# GPSSDver2.net
KiCad netlist of a schematic drawn in EAGLE
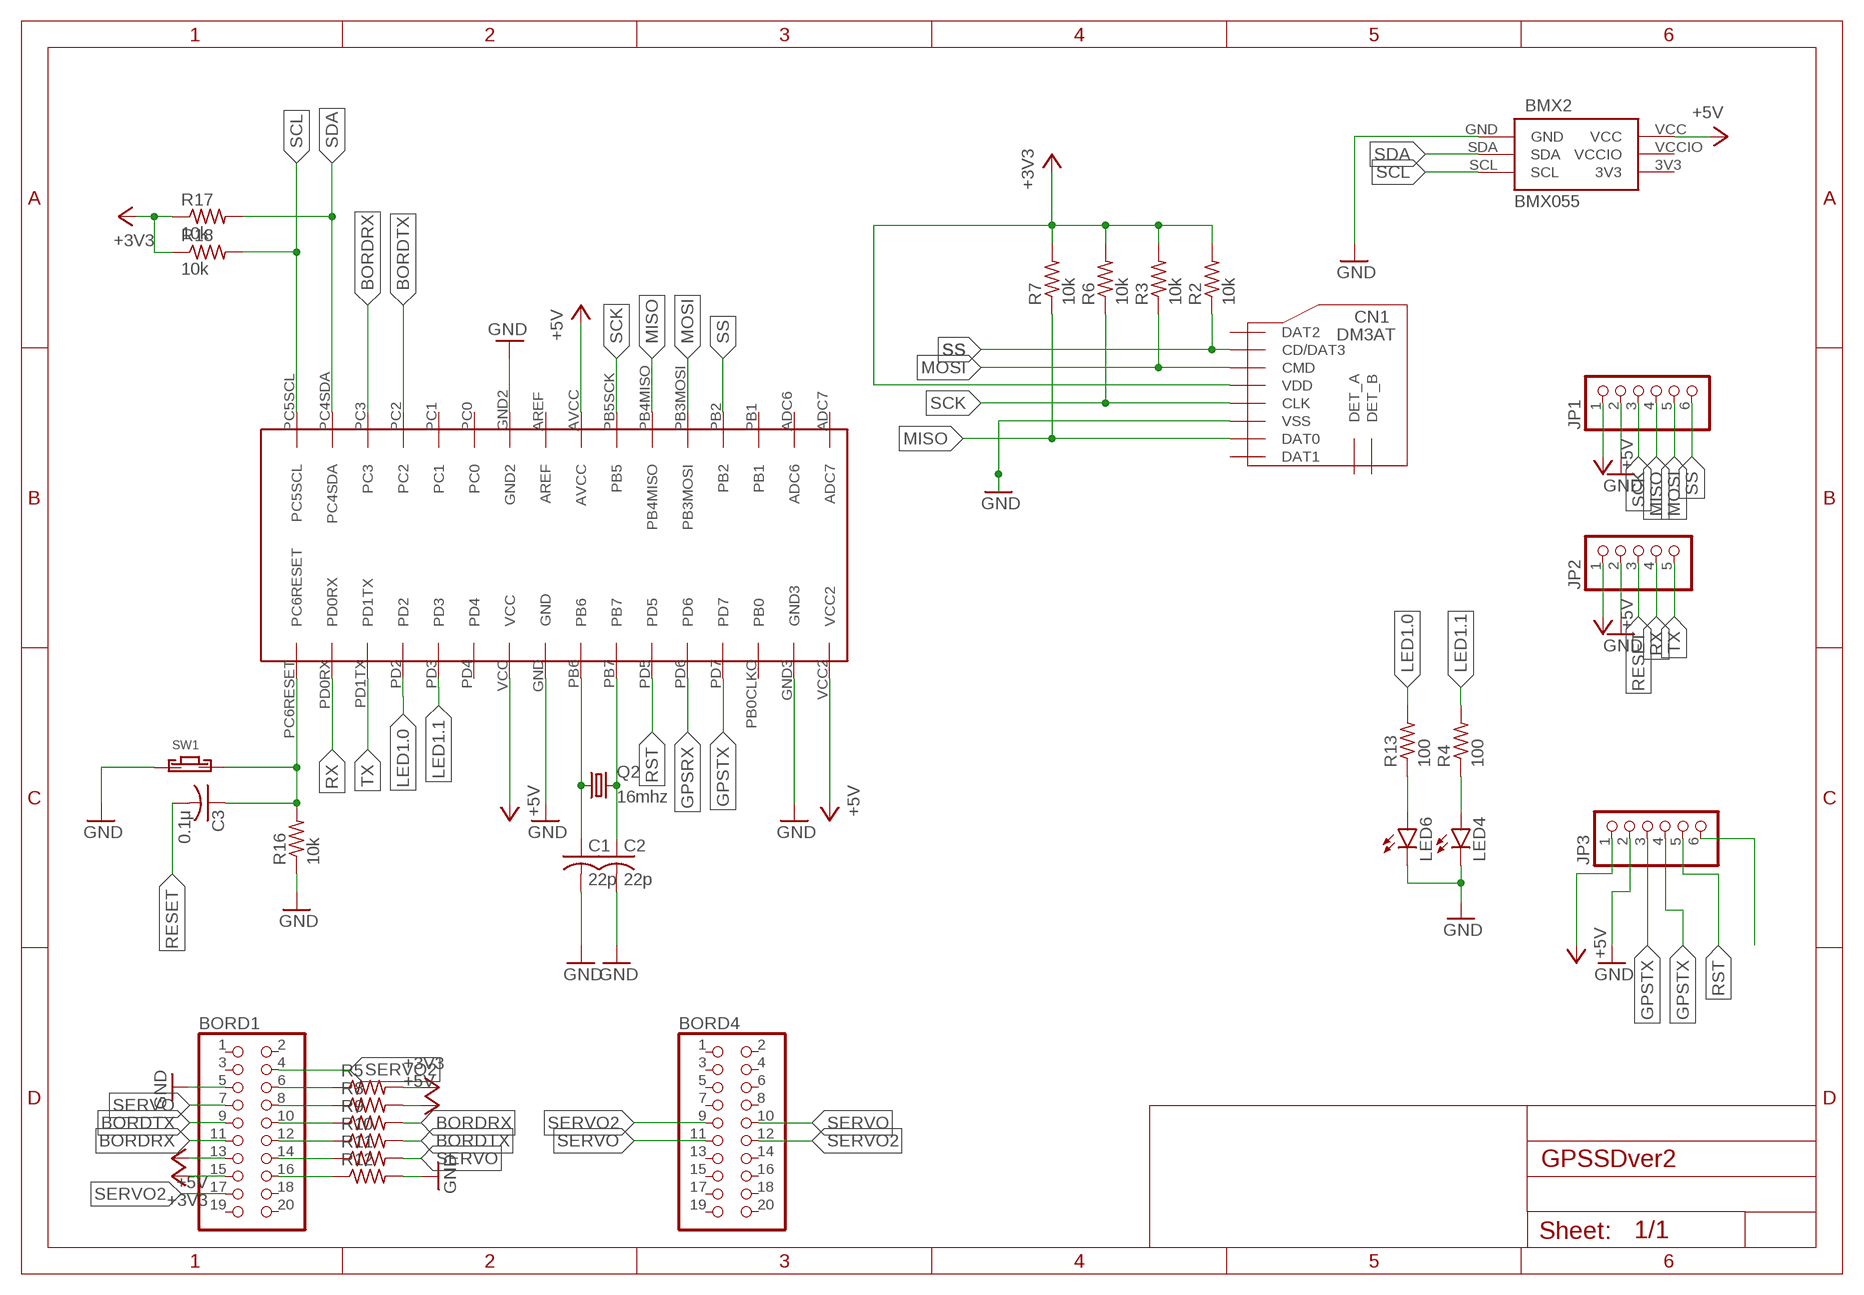
[diagram p0: schematic, sheet 1]

(export (version "E")
  (design (tool "Eeschema 10.0.6"))
  (components
    (comp (ref "BMX2")
      (value "BMX055")
      (footprint "eagle-import:BMX055")
      (libsource (lib "eagle-import") (part "BMX055"))
    )
    (comp (ref "BORD1")
      (value "PINHD-2X10/90")
      (footprint "eagle-import:2X10_90")
      (libsource (lib "eagle-import") (part "PINHD-2X10/90"))
    )
    (comp (ref "BORD4")
      (value "PINHD-2X10/90")
      (footprint "eagle-import:2X10_90")
      (libsource (lib "eagle-import") (part "PINHD-2X10/90"))
    )
    (comp (ref "C1")
      (value "22p")
      (footprint "eagle-import:C1608")
      (libsource (lib "eagle-import") (part "C-USC1608"))
    )
    (comp (ref "C2")
      (value "22p")
      (footprint "eagle-import:C1608")
      (libsource (lib "eagle-import") (part "C-USC1608"))
    )
    (comp (ref "C3")
      (value "0.1μ")
      (footprint "eagle-import:C1608")
      (libsource (lib "eagle-import") (part "C-USC1608"))
    )
    (comp (ref "CN1")
      (value "DM3AT")
      (footprint "eagle-import:DM3AT")
      (libsource (lib "eagle-import") (part "DM3AT"))
    )
    (comp (ref "JP1")
      (value "PINHD-1X6")
      (footprint "eagle-import:1X06")
      (libsource (lib "eagle-import") (part "PINHD-1X6"))
    )
    (comp (ref "JP2")
      (value "PINHD-1X5")
      (footprint "eagle-import:1X05")
      (libsource (lib "eagle-import") (part "PINHD-1X5"))
    )
    (comp (ref "JP3")
      (value "PINHD-1X6")
      (footprint "eagle-import:1X06")
      (libsource (lib "eagle-import") (part "PINHD-1X6"))
    )
    (comp (ref "LED4")
      (value "LED5MM")
      (footprint "eagle-import:LED5MM")
      (libsource (lib "eagle-import") (part "LED5MM"))
    )
    (comp (ref "LED6")
      (value "LED5MM")
      (footprint "eagle-import:LED5MM")
      (libsource (lib "eagle-import") (part "LED5MM"))
    )
    (comp (ref "Q2")
      (value "16mhz")
      (footprint "eagle-import:HC49UP")
      (libsource (lib "eagle-import") (part "CRYSTALHC49UP"))
    )
    (comp (ref "R2")
      (value "10k")
      (footprint "eagle-import:R0603")
      (libsource (lib "eagle-import") (part "R-US_R0603"))
    )
    (comp (ref "R3")
      (value "10k")
      (footprint "eagle-import:R0603")
      (libsource (lib "eagle-import") (part "R-US_R0603"))
    )
    (comp (ref "R4")
      (value "100")
      (footprint "eagle-import:R0603")
      (libsource (lib "eagle-import") (part "R-US_R0603"))
    )
    (comp (ref "R5")
      (value "R-US_R0603")
      (footprint "eagle-import:R0603")
      (libsource (lib "eagle-import") (part "R-US_R0603"))
    )
    (comp (ref "R6")
      (value "10k")
      (footprint "eagle-import:R0603")
      (libsource (lib "eagle-import") (part "R-US_R0603"))
    )
    (comp (ref "R7")
      (value "10k")
      (footprint "eagle-import:R0603")
      (libsource (lib "eagle-import") (part "R-US_R0603"))
    )
    (comp (ref "R8")
      (value "R-US_R0603")
      (footprint "eagle-import:R0603")
      (libsource (lib "eagle-import") (part "R-US_R0603"))
    )
    (comp (ref "R9")
      (value "R-US_R0603")
      (footprint "eagle-import:R0603")
      (libsource (lib "eagle-import") (part "R-US_R0603"))
    )
    (comp (ref "R10")
      (value "R-US_R0603")
      (footprint "eagle-import:R0603")
      (libsource (lib "eagle-import") (part "R-US_R0603"))
    )
    (comp (ref "R11")
      (value "R-US_R0603")
      (footprint "eagle-import:R0603")
      (libsource (lib "eagle-import") (part "R-US_R0603"))
    )
    (comp (ref "R12")
      (value "R-US_R0603")
      (footprint "eagle-import:R0603")
      (libsource (lib "eagle-import") (part "R-US_R0603"))
    )
    (comp (ref "R13")
      (value "100")
      (footprint "eagle-import:R0603")
      (libsource (lib "eagle-import") (part "R-US_R0603"))
    )
    (comp (ref "R16")
      (value "10k")
      (footprint "eagle-import:R0603")
      (libsource (lib "eagle-import") (part "R-US_R0603"))
    )
    (comp (ref "R17")
      (value "10k")
      (footprint "eagle-import:R0603")
      (libsource (lib "eagle-import") (part "R-US_R0603"))
    )
    (comp (ref "R18")
      (value "10k")
      (footprint "eagle-import:R0603")
      (libsource (lib "eagle-import") (part "R-US_R0603"))
    )
    (comp (ref "SW1")
      (value "TVAF06-A020B-R")
      (footprint "eagle-import:TVAF06-A020B-R")
      (libsource (lib "eagle-import") (part "TVAF06-A020B-R"))
    )
    (comp (ref "U$3")
      (value "ATMEGA328P-AU")
      (footprint "eagle-import:ATMEGA328P-AU")
      (libsource (lib "eagle-import") (part "ATMEGA328P-AU"))
    )
  )
  (nets
    (net (code "1") (name "+3V3") (class "Default")
      (node (ref "BORD1") (pin "15") (pinfunction "15_15") (pintype "passive"))
      (node (ref "CN1") (pin "VDD") (pinfunction "VDD_VDD") (pintype "bidirectional"))
      (node (ref "R17") (pin "1") (pinfunction "1_1") (pintype "passive"))
      (node (ref "R18") (pin "1") (pinfunction "1_1") (pintype "passive"))
      (node (ref "R2") (pin "2") (pinfunction "2_2") (pintype "passive"))
      (node (ref "R3") (pin "2") (pinfunction "2_2") (pintype "passive"))
      (node (ref "R5") (pin "2") (pinfunction "2_2") (pintype "passive"))
      (node (ref "R6") (pin "2") (pinfunction "2_2") (pintype "passive"))
      (node (ref "R7") (pin "2") (pinfunction "2_2") (pintype "passive"))
    )
    (net (code "2") (name "+5V") (class "Default")
      (node (ref "BMX2") (pin "VCC") (pinfunction "VCC_VCC") (pintype "power_in"))
      (node (ref "BORD1") (pin "13") (pinfunction "13_13") (pintype "passive"))
      (node (ref "JP1") (pin "1") (pinfunction "1_1") (pintype "passive"))
      (node (ref "JP2") (pin "1") (pinfunction "1_1") (pintype "passive"))
      (node (ref "JP3") (pin "1") (pinfunction "1_1") (pintype "passive"))
      (node (ref "R8") (pin "2") (pinfunction "2_2") (pintype "passive"))
      (node (ref "U$3") (pin "AVCC") (pinfunction "AVCC_AVCC") (pintype "bidirectional"))
      (node (ref "U$3") (pin "VCC") (pinfunction "VCC_VCC") (pintype "bidirectional"))
      (node (ref "U$3") (pin "VCC2") (pinfunction "VCC2_VCC2") (pintype "bidirectional"))
    )
    (net (code "3") (name "/3V3") (class "Default")
      (node (ref "BMX2") (pin "3V3") (pinfunction "3V3_3V3") (pintype "power_in"))
    )
    (net (code "4") (name "/VCCIO") (class "Default")
      (node (ref "BMX2") (pin "VCCIO") (pinfunction "VCCIO_VCCIO") (pintype "power_in"))
    )
    (net (code "5") (name "BORDRX") (class "Default")
      (node (ref "BORD1") (pin "11") (pinfunction "11_11") (pintype "passive"))
      (node (ref "R9") (pin "2") (pinfunction "2_2") (pintype "passive"))
      (node (ref "U$3") (pin "PC3") (pinfunction "PC3_PC3") (pintype "bidirectional"))
    )
    (net (code "6") (name "BORDTX") (class "Default")
      (node (ref "BORD1") (pin "9") (pinfunction "9_9") (pintype "passive"))
      (node (ref "R10") (pin "2") (pinfunction "2_2") (pintype "passive"))
      (node (ref "U$3") (pin "PC2") (pinfunction "PC2_PC2") (pintype "bidirectional"))
    )
    (net (code "7") (name "GND") (class "Default")
      (node (ref "BMX2") (pin "GND") (pinfunction "GND_GND") (pintype "power_in"))
      (node (ref "BORD1") (pin "5") (pinfunction "5_5") (pintype "passive"))
      (node (ref "C1") (pin "2") (pinfunction "2_2") (pintype "passive"))
      (node (ref "C2") (pin "2") (pinfunction "2_2") (pintype "passive"))
      (node (ref "CN1") (pin "VSS") (pinfunction "VSS_VSS") (pintype "bidirectional"))
      (node (ref "JP1") (pin "2") (pinfunction "2_2") (pintype "passive"))
      (node (ref "JP2") (pin "2") (pinfunction "2_2") (pintype "passive"))
      (node (ref "JP3") (pin "2") (pinfunction "2_2") (pintype "passive"))
      (node (ref "LED4") (pin "K") (pinfunction "C_K") (pintype "passive"))
      (node (ref "LED6") (pin "K") (pinfunction "C_K") (pintype "passive"))
      (node (ref "R12") (pin "2") (pinfunction "2_2") (pintype "passive"))
      (node (ref "R16") (pin "1") (pinfunction "1_1") (pintype "passive"))
      (node (ref "SW1") (pin "P$1") (pinfunction "P$1_P$1") (pintype "bidirectional"))
      (node (ref "U$3") (pin "GND") (pinfunction "GND_GND") (pintype "bidirectional"))
      (node (ref "U$3") (pin "GND2") (pinfunction "GND2_GND2") (pintype "bidirectional"))
      (node (ref "U$3") (pin "GND3") (pinfunction "GND3_GND3") (pintype "bidirectional"))
    )
    (net (code "8") (name "GPSRX") (class "Default")
      (node (ref "U$3") (pin "PD6") (pinfunction "PD6_PD6") (pintype "bidirectional"))
    )
    (net (code "9") (name "GPSTX") (class "Default")
      (node (ref "JP3") (pin "3") (pinfunction "3_3") (pintype "passive"))
      (node (ref "JP3") (pin "4") (pinfunction "4_4") (pintype "passive"))
      (node (ref "U$3") (pin "PD7") (pinfunction "PD7_PD7") (pintype "bidirectional"))
    )
    (net (code "10") (name "LED1.0") (class "Default")
      (node (ref "R13") (pin "2") (pinfunction "2_2") (pintype "passive"))
      (node (ref "U$3") (pin "PD2") (pinfunction "PD2_PD2") (pintype "bidirectional"))
    )
    (net (code "11") (name "LED1.1") (class "Default")
      (node (ref "R4") (pin "2") (pinfunction "2_2") (pintype "passive"))
      (node (ref "U$3") (pin "PD3") (pinfunction "PD3_PD3") (pintype "bidirectional"))
    )
    (net (code "12") (name "MISO") (class "Default")
      (node (ref "CN1") (pin "DAT0") (pinfunction "DAT0_DAT0") (pintype "bidirectional"))
      (node (ref "JP1") (pin "4") (pinfunction "4_4") (pintype "passive"))
      (node (ref "R7") (pin "1") (pinfunction "1_1") (pintype "passive"))
      (node (ref "U$3") (pin "PB4MISO") (pinfunction "PB4MISO_PB4MISO") (pintype "bidirectional"))
    )
    (net (code "13") (name "MOSI") (class "Default")
      (node (ref "CN1") (pin "CMD") (pinfunction "CMD_CMD") (pintype "bidirectional"))
      (node (ref "JP1") (pin "5") (pinfunction "5_5") (pintype "passive"))
      (node (ref "R3") (pin "1") (pinfunction "1_1") (pintype "passive"))
      (node (ref "U$3") (pin "PB3MOSI") (pinfunction "PB3MOSI_PB3MOSI") (pintype "bidirectional"))
    )
    (net (code "14") (name "Net-(BORD1-Pad6)") (class "Default")
      (node (ref "BORD1") (pin "6") (pinfunction "6_6") (pintype "passive"))
      (node (ref "R5") (pin "1") (pinfunction "1_1") (pintype "passive"))
    )
    (net (code "15") (name "Net-(BORD1-Pad8)") (class "Default")
      (node (ref "BORD1") (pin "8") (pinfunction "8_8") (pintype "passive"))
      (node (ref "R8") (pin "1") (pinfunction "1_1") (pintype "passive"))
    )
    (net (code "16") (name "Net-(BORD1-Pad10)") (class "Default")
      (node (ref "BORD1") (pin "10") (pinfunction "10_10") (pintype "passive"))
      (node (ref "R9") (pin "1") (pinfunction "1_1") (pintype "passive"))
    )
    (net (code "17") (name "Net-(BORD1-Pad12)") (class "Default")
      (node (ref "BORD1") (pin "12") (pinfunction "12_12") (pintype "passive"))
      (node (ref "R10") (pin "1") (pinfunction "1_1") (pintype "passive"))
    )
    (net (code "18") (name "Net-(BORD1-Pad14)") (class "Default")
      (node (ref "BORD1") (pin "14") (pinfunction "14_14") (pintype "passive"))
      (node (ref "R11") (pin "1") (pinfunction "1_1") (pintype "passive"))
    )
    (net (code "19") (name "Net-(BORD1-Pad16)") (class "Default")
      (node (ref "BORD1") (pin "16") (pinfunction "16_16") (pintype "passive"))
      (node (ref "R12") (pin "1") (pinfunction "1_1") (pintype "passive"))
    )
    (net (code "20") (name "Net-(C1-Pad1)") (class "Default")
      (node (ref "C1") (pin "1") (pinfunction "1_1") (pintype "passive"))
      (node (ref "Q2") (pin "1") (pinfunction "1_1") (pintype "passive"))
      (node (ref "U$3") (pin "PB6") (pinfunction "PB6_PB6") (pintype "bidirectional"))
    )
    (net (code "21") (name "Net-(C2-Pad1)") (class "Default")
      (node (ref "C2") (pin "1") (pinfunction "1_1") (pintype "passive"))
      (node (ref "Q2") (pin "2") (pinfunction "2_2") (pintype "passive"))
      (node (ref "U$3") (pin "PB7") (pinfunction "PB7_PB7") (pintype "bidirectional"))
    )
    (net (code "22") (name "Net-(C3-Pad1)") (class "Default")
      (node (ref "C3") (pin "1") (pinfunction "1_1") (pintype "passive"))
      (node (ref "R16") (pin "2") (pinfunction "2_2") (pintype "passive"))
      (node (ref "SW1") (pin "P$2") (pinfunction "P$2_P$2") (pintype "bidirectional"))
      (node (ref "U$3") (pin "PC6RESET") (pinfunction "PC6RESET_PC6RESET") (pintype "bidirectional"))
    )
    (net (code "23") (name "Net-(LED4-PadA)") (class "Default")
      (node (ref "LED4") (pin "A") (pinfunction "A_A") (pintype "passive"))
      (node (ref "R4") (pin "1") (pinfunction "1_1") (pintype "passive"))
    )
    (net (code "24") (name "Net-(LED6-PadA)") (class "Default")
      (node (ref "LED6") (pin "A") (pinfunction "A_A") (pintype "passive"))
      (node (ref "R13") (pin "1") (pinfunction "1_1") (pintype "passive"))
    )
    (net (code "25") (name "RESET") (class "Default")
      (node (ref "C3") (pin "2") (pinfunction "2_2") (pintype "passive"))
      (node (ref "JP2") (pin "3") (pinfunction "3_3") (pintype "passive"))
    )
    (net (code "26") (name "RST") (class "Default")
      (node (ref "JP3") (pin "5") (pinfunction "5_5") (pintype "passive"))
      (node (ref "U$3") (pin "PD5") (pinfunction "PD5_PD5") (pintype "bidirectional"))
    )
    (net (code "27") (name "RX") (class "Default")
      (node (ref "JP2") (pin "4") (pinfunction "4_4") (pintype "passive"))
      (node (ref "U$3") (pin "PD0RX") (pinfunction "PD0RX_PD0RX") (pintype "bidirectional"))
    )
    (net (code "28") (name "SCK") (class "Default")
      (node (ref "CN1") (pin "CLK") (pinfunction "CLK_CLK") (pintype "bidirectional"))
      (node (ref "JP1") (pin "3") (pinfunction "3_3") (pintype "passive"))
      (node (ref "R6") (pin "1") (pinfunction "1_1") (pintype "passive"))
      (node (ref "U$3") (pin "PB5SCK") (pinfunction "PB5_PB5SCK") (pintype "bidirectional"))
    )
    (net (code "29") (name "SCL") (class "Default")
      (node (ref "BMX2") (pin "SCL") (pinfunction "SCL_SCL") (pintype "bidirectional"))
      (node (ref "R18") (pin "2") (pinfunction "2_2") (pintype "passive"))
      (node (ref "U$3") (pin "PC5SCL") (pinfunction "PC5SCL_PC5SCL") (pintype "bidirectional"))
    )
    (net (code "30") (name "SDA") (class "Default")
      (node (ref "BMX2") (pin "SDA") (pinfunction "SDA_SDA") (pintype "bidirectional"))
      (node (ref "R17") (pin "2") (pinfunction "2_2") (pintype "passive"))
      (node (ref "U$3") (pin "PC4SDA") (pinfunction "PC4SDA_PC4SDA") (pintype "bidirectional"))
    )
    (net (code "31") (name "SERVO") (class "Default")
      (node (ref "BORD1") (pin "7") (pinfunction "7_7") (pintype "passive"))
      (node (ref "BORD4") (pin "10") (pinfunction "10_10") (pintype "passive"))
      (node (ref "BORD4") (pin "11") (pinfunction "11_11") (pintype "passive"))
      (node (ref "R11") (pin "2") (pinfunction "2_2") (pintype "passive"))
    )
    (net (code "32") (name "SERVO2") (class "Default")
      (node (ref "BORD1") (pin "17") (pinfunction "17_17") (pintype "passive"))
      (node (ref "BORD1") (pin "4") (pinfunction "4_4") (pintype "passive"))
      (node (ref "BORD4") (pin "12") (pinfunction "12_12") (pintype "passive"))
      (node (ref "BORD4") (pin "9") (pinfunction "9_9") (pintype "passive"))
    )
    (net (code "33") (name "SS") (class "Default")
      (node (ref "CN1") (pin "CD/DAT3") (pinfunction "CD/DAT3_CD/DAT3") (pintype "bidirectional"))
      (node (ref "JP1") (pin "6") (pinfunction "6_6") (pintype "passive"))
      (node (ref "R2") (pin "1") (pinfunction "1_1") (pintype "passive"))
      (node (ref "U$3") (pin "PB2") (pinfunction "PB2_PB2") (pintype "bidirectional"))
    )
    (net (code "34") (name "TX") (class "Default")
      (node (ref "JP2") (pin "5") (pinfunction "5_5") (pintype "passive"))
      (node (ref "U$3") (pin "PD1TX") (pinfunction "PD1TX_PD1TX") (pintype "bidirectional"))
    )
    (net (code "35") (name "unconnected-(BORD1-Pad1)") (class "Default")
      (node (ref "BORD1") (pin "1") (pinfunction "1_1") (pintype "passive"))
    )
    (net (code "36") (name "unconnected-(BORD1-Pad2)") (class "Default")
      (node (ref "BORD1") (pin "2") (pinfunction "2_2") (pintype "passive"))
    )
    (net (code "37") (name "unconnected-(BORD1-Pad3)") (class "Default")
      (node (ref "BORD1") (pin "3") (pinfunction "3_3") (pintype "passive"))
    )
    (net (code "38") (name "unconnected-(BORD1-Pad18)") (class "Default")
      (node (ref "BORD1") (pin "18") (pinfunction "18_18") (pintype "passive"))
    )
    (net (code "39") (name "unconnected-(BORD1-Pad19)") (class "Default")
      (node (ref "BORD1") (pin "19") (pinfunction "19_19") (pintype "passive"))
    )
    (net (code "40") (name "unconnected-(BORD1-Pad20)") (class "Default")
      (node (ref "BORD1") (pin "20") (pinfunction "20_20") (pintype "passive"))
    )
    (net (code "41") (name "unconnected-(BORD4-Pad1)") (class "Default")
      (node (ref "BORD4") (pin "1") (pinfunction "1_1") (pintype "passive"))
    )
    (net (code "42") (name "unconnected-(BORD4-Pad2)") (class "Default")
      (node (ref "BORD4") (pin "2") (pinfunction "2_2") (pintype "passive"))
    )
    (net (code "43") (name "unconnected-(BORD4-Pad3)") (class "Default")
      (node (ref "BORD4") (pin "3") (pinfunction "3_3") (pintype "passive"))
    )
    (net (code "44") (name "unconnected-(BORD4-Pad4)") (class "Default")
      (node (ref "BORD4") (pin "4") (pinfunction "4_4") (pintype "passive"))
    )
    (net (code "45") (name "unconnected-(BORD4-Pad5)") (class "Default")
      (node (ref "BORD4") (pin "5") (pinfunction "5_5") (pintype "passive"))
    )
    (net (code "46") (name "unconnected-(BORD4-Pad6)") (class "Default")
      (node (ref "BORD4") (pin "6") (pinfunction "6_6") (pintype "passive"))
    )
    (net (code "47") (name "unconnected-(BORD4-Pad7)") (class "Default")
      (node (ref "BORD4") (pin "7") (pinfunction "7_7") (pintype "passive"))
    )
    (net (code "48") (name "unconnected-(BORD4-Pad8)") (class "Default")
      (node (ref "BORD4") (pin "8") (pinfunction "8_8") (pintype "passive"))
    )
    (net (code "49") (name "unconnected-(BORD4-Pad13)") (class "Default")
      (node (ref "BORD4") (pin "13") (pinfunction "13_13") (pintype "passive"))
    )
    (net (code "50") (name "unconnected-(BORD4-Pad14)") (class "Default")
      (node (ref "BORD4") (pin "14") (pinfunction "14_14") (pintype "passive"))
    )
    (net (code "51") (name "unconnected-(BORD4-Pad15)") (class "Default")
      (node (ref "BORD4") (pin "15") (pinfunction "15_15") (pintype "passive"))
    )
    (net (code "52") (name "unconnected-(BORD4-Pad16)") (class "Default")
      (node (ref "BORD4") (pin "16") (pinfunction "16_16") (pintype "passive"))
    )
    (net (code "53") (name "unconnected-(BORD4-Pad17)") (class "Default")
      (node (ref "BORD4") (pin "17") (pinfunction "17_17") (pintype "passive"))
    )
    (net (code "54") (name "unconnected-(BORD4-Pad18)") (class "Default")
      (node (ref "BORD4") (pin "18") (pinfunction "18_18") (pintype "passive"))
    )
    (net (code "55") (name "unconnected-(BORD4-Pad19)") (class "Default")
      (node (ref "BORD4") (pin "19") (pinfunction "19_19") (pintype "passive"))
    )
    (net (code "56") (name "unconnected-(BORD4-Pad20)") (class "Default")
      (node (ref "BORD4") (pin "20") (pinfunction "20_20") (pintype "passive"))
    )
    (net (code "57") (name "unconnected-(CN1-PadDAT1)") (class "Default")
      (node (ref "CN1") (pin "DAT1") (pinfunction "DAT1_DAT1") (pintype "bidirectional"))
    )
    (net (code "58") (name "unconnected-(CN1-PadDAT2)") (class "Default")
      (node (ref "CN1") (pin "DAT2") (pinfunction "DAT2_DAT2") (pintype "bidirectional"))
    )
    (net (code "59") (name "unconnected-(CN1-PadDET_A)") (class "Default")
      (node (ref "CN1") (pin "DET_A") (pinfunction "DET_A_DET_A") (pintype "bidirectional"))
    )
    (net (code "60") (name "unconnected-(CN1-PadDET_B)") (class "Default")
      (node (ref "CN1") (pin "DET_B") (pinfunction "DET_B_DET_B") (pintype "bidirectional"))
    )
    (net (code "61") (name "unconnected-(JP3-Pad6)") (class "Default")
      (node (ref "JP3") (pin "6") (pinfunction "6_6") (pintype "passive"))
    )
    (net (code "62") (name "unconnected-(U$3-PB0-PadPB0CLKO)") (class "Default")
      (node (ref "U$3") (pin "PB0CLKO") (pinfunction "PB0_PB0CLKO") (pintype "bidirectional"))
    )
    (net (code "63") (name "unconnected-(U$3-PadADC6)") (class "Default")
      (node (ref "U$3") (pin "ADC6") (pinfunction "ADC6_ADC6") (pintype "bidirectional"))
    )
    (net (code "64") (name "unconnected-(U$3-PadADC7)") (class "Default")
      (node (ref "U$3") (pin "ADC7") (pinfunction "ADC7_ADC7") (pintype "bidirectional"))
    )
    (net (code "65") (name "unconnected-(U$3-PadAREF)") (class "Default")
      (node (ref "U$3") (pin "AREF") (pinfunction "AREF_AREF") (pintype "bidirectional"))
    )
    (net (code "66") (name "unconnected-(U$3-PadPB1)") (class "Default")
      (node (ref "U$3") (pin "PB1") (pinfunction "PB1_PB1") (pintype "bidirectional"))
    )
    (net (code "67") (name "unconnected-(U$3-PadPC0)") (class "Default")
      (node (ref "U$3") (pin "PC0") (pinfunction "PC0_PC0") (pintype "bidirectional"))
    )
    (net (code "68") (name "unconnected-(U$3-PadPC1)") (class "Default")
      (node (ref "U$3") (pin "PC1") (pinfunction "PC1_PC1") (pintype "bidirectional"))
    )
    (net (code "69") (name "unconnected-(U$3-PadPD4)") (class "Default")
      (node (ref "U$3") (pin "PD4") (pinfunction "PD4_PD4") (pintype "bidirectional"))
    )
  )
)
